# Pi1541_IEC.net
KiCad netlist of a schematic drawn in EAGLE
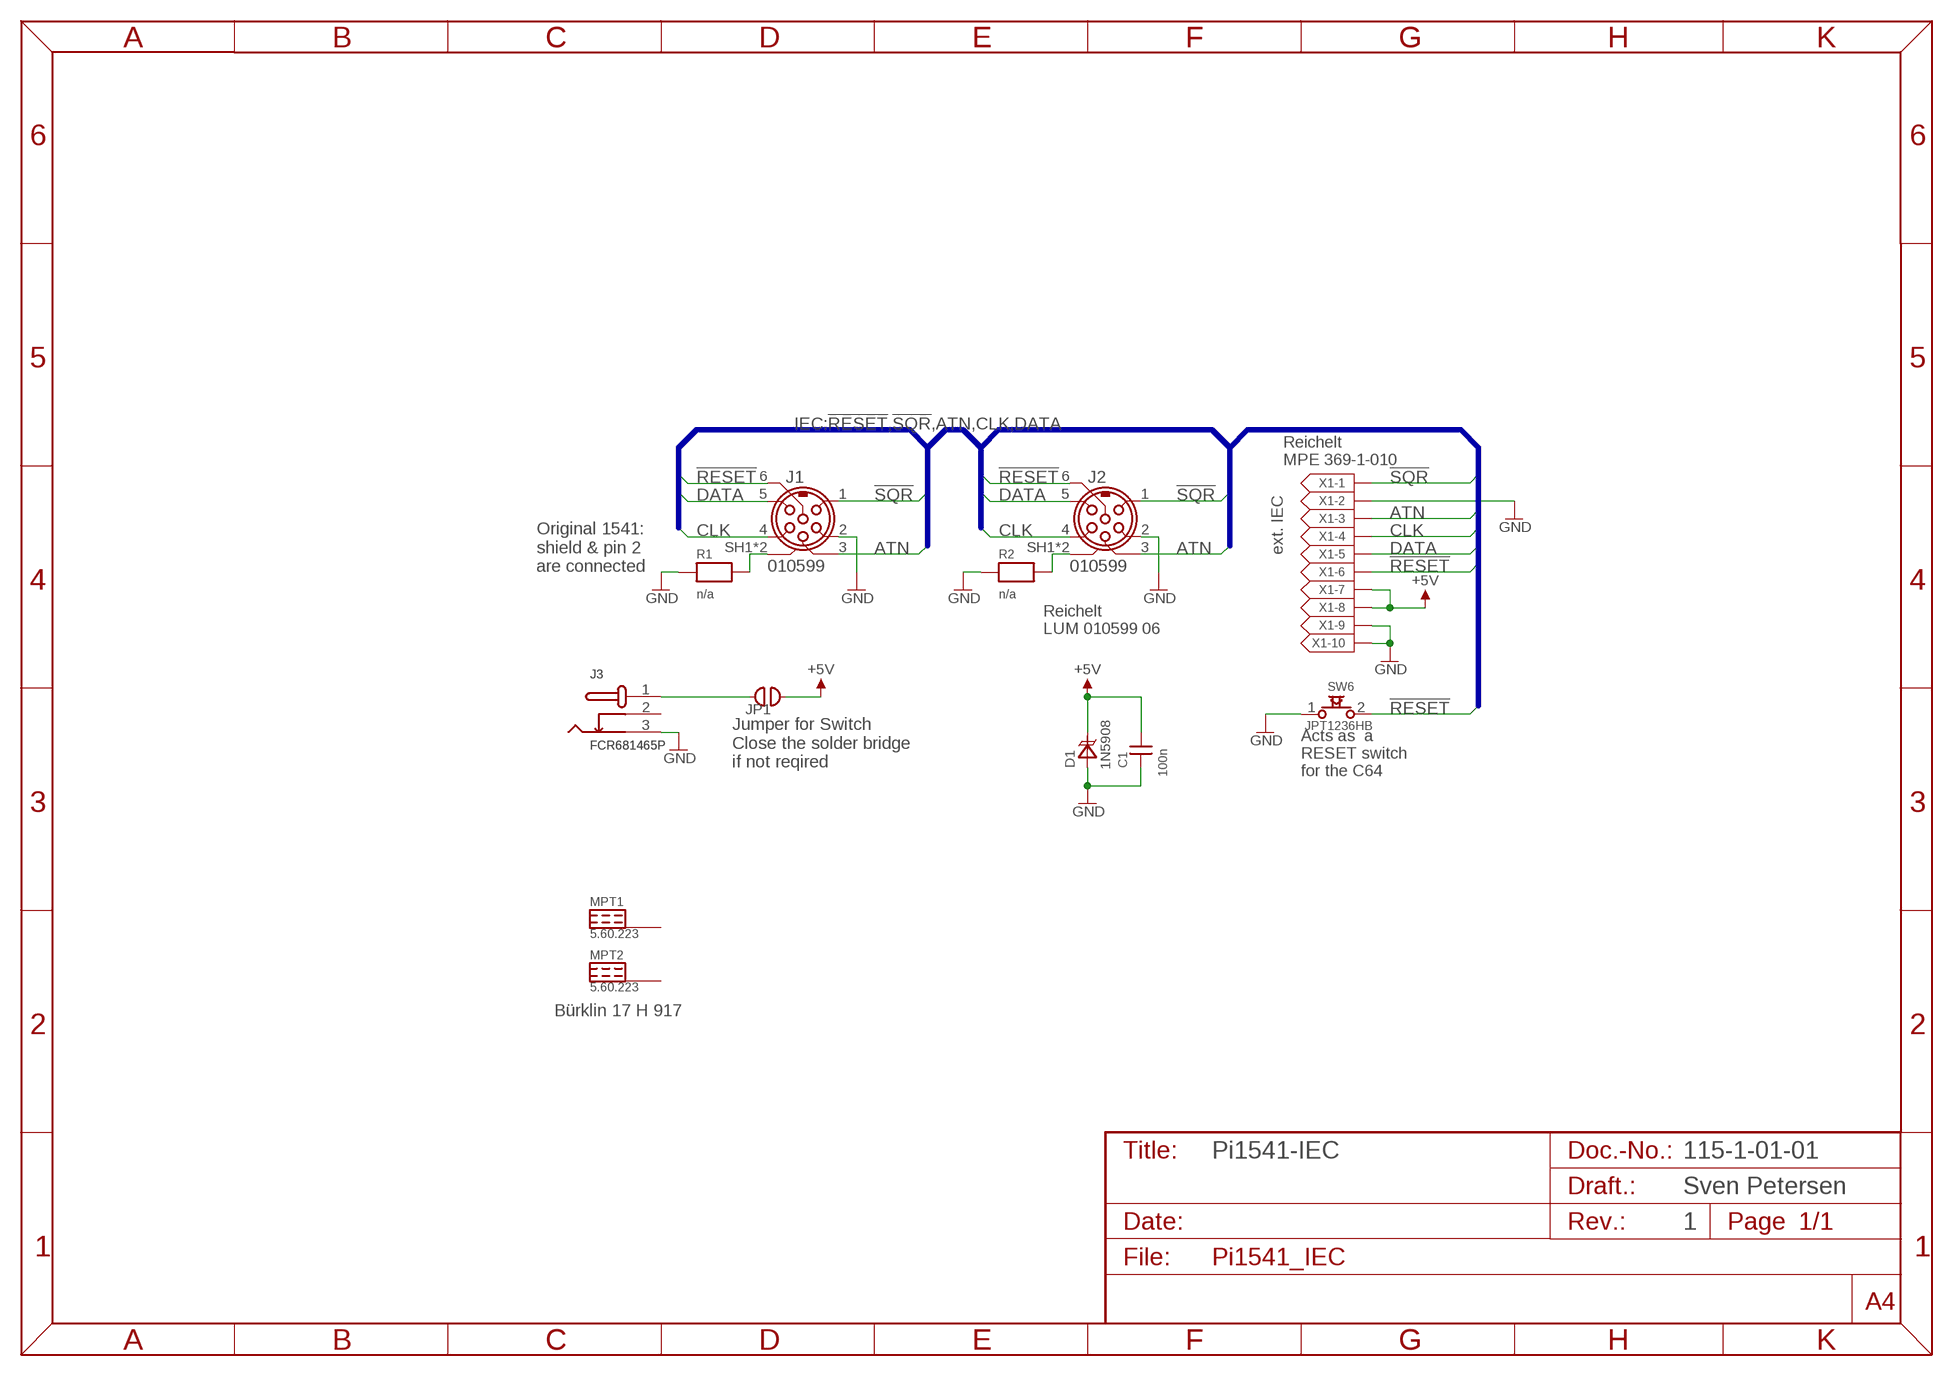
[diagram p0: schematic, sheet 1]

(export (version "E")
  (design (tool "Eeschema 10.0.6"))
  (components
    (comp (ref "C1")
      (value "100n")
      (footprint "eagle-import:C-2,5")
      (libsource (lib "eagle-import") (part "CAP01"))
    )
    (comp (ref "D1")
      (value "1N5908")
      (footprint "eagle-import:CB429")
      (libsource (lib "eagle-import") (part "1N5908"))
    )
    (comp (ref "J1")
      (value "010599")
      (footprint "eagle-import:010599")
      (libsource (lib "eagle-import") (part "010599"))
    )
    (comp (ref "J2")
      (value "010599")
      (footprint "eagle-import:010599")
      (libsource (lib "eagle-import") (part "010599"))
    )
    (comp (ref "J3")
      (value "FCR681465P")
      (footprint "eagle-import:FCR681465P")
      (libsource (lib "eagle-import") (part "FCR681465P"))
    )
    (comp (ref "JP1")
      (value "COMBI_2P")
      (footprint "eagle-import:COMBI-2P")
      (libsource (lib "eagle-import") (part "COMBI_2P"))
    )
    (comp (ref "MPT1")
      (value "5.60.223")
      (footprint "eagle-import:5.60.223")
      (libsource (lib "eagle-import") (part "5.60.223"))
    )
    (comp (ref "MPT2")
      (value "5.60.223")
      (footprint "eagle-import:5.60.223")
      (libsource (lib "eagle-import") (part "5.60.223"))
    )
    (comp (ref "R1")
      (value "n/a")
      (footprint "eagle-import:0805")
      (libsource (lib "eagle-import") (part "R-0805"))
    )
    (comp (ref "R2")
      (value "n/a")
      (footprint "eagle-import:0805")
      (libsource (lib "eagle-import") (part "R-0805"))
    )
    (comp (ref "SW6")
      (value "JPT1236HB")
      (footprint "eagle-import:JTP_1236HB")
      (libsource (lib "eagle-import") (part "JPT1236HB"))
    )
    (comp (ref "X1")
      (value "369-1-010")
      (footprint "eagle-import:MICMA10B")
      (libsource (lib "eagle-import") (part "MICMA10B-THT"))
    )
  )
  (nets
    (net (code "2") (name "+5V") (class "Default")
      (node (ref "C1") (pin "2") (pinfunction "2_2") (pintype "passive"))
      (node (ref "D1") (pin "K") (pinfunction "K_K") (pintype "passive"))
      (node (ref "JP1") (pin "2") (pinfunction "2_2") (pintype "passive"))
      (node (ref "X1") (pin "7") (pinfunction "1_7") (pintype "bidirectional"))
      (node (ref "X1") (pin "8") (pinfunction "1_8") (pintype "bidirectional"))
    )
    (net (code "3") (name "/ATN") (class "Default")
      (node (ref "J1") (pin "3") (pinfunction "3_3") (pintype "bidirectional"))
      (node (ref "J2") (pin "3") (pinfunction "3_3") (pintype "bidirectional"))
      (node (ref "X1") (pin "3") (pinfunction "1_3") (pintype "bidirectional"))
    )
    (net (code "4") (name "/CLK") (class "Default")
      (node (ref "J1") (pin "4") (pinfunction "4_4") (pintype "bidirectional"))
      (node (ref "J2") (pin "4") (pinfunction "4_4") (pintype "bidirectional"))
      (node (ref "X1") (pin "4") (pinfunction "1_4") (pintype "bidirectional"))
    )
    (net (code "5") (name "/DATA") (class "Default")
      (node (ref "J1") (pin "5") (pinfunction "5_5") (pintype "bidirectional"))
      (node (ref "J2") (pin "5") (pinfunction "5_5") (pintype "bidirectional"))
      (node (ref "X1") (pin "5") (pinfunction "1_5") (pintype "bidirectional"))
    )
    (net (code "7") (name "/~{RESET}") (class "Default")
      (node (ref "J1") (pin "6") (pinfunction "6_6") (pintype "bidirectional"))
      (node (ref "J2") (pin "6") (pinfunction "6_6") (pintype "bidirectional"))
      (node (ref "SW6") (pin "2") (pinfunction "2_2") (pintype "passive"))
      (node (ref "X1") (pin "6") (pinfunction "1_6") (pintype "bidirectional"))
    )
    (net (code "8") (name "/~{SQR}") (class "Default")
      (node (ref "J1") (pin "1") (pinfunction "1_1") (pintype "bidirectional"))
      (node (ref "J2") (pin "1") (pinfunction "1_1") (pintype "bidirectional"))
      (node (ref "X1") (pin "1") (pinfunction "1_1") (pintype "bidirectional"))
    )
    (net (code "9") (name "GND") (class "Default")
      (node (ref "C1") (pin "1") (pinfunction "1_1") (pintype "passive"))
      (node (ref "D1") (pin "A") (pinfunction "A_A") (pintype "passive"))
      (node (ref "J1") (pin "2") (pinfunction "2_2") (pintype "bidirectional"))
      (node (ref "J2") (pin "2") (pinfunction "2_2") (pintype "bidirectional"))
      (node (ref "J3") (pin "3") (pinfunction "3_3") (pintype "bidirectional"))
      (node (ref "R1") (pin "1") (pinfunction "1_1") (pintype "passive"))
      (node (ref "R2") (pin "1") (pinfunction "1_1") (pintype "passive"))
      (node (ref "SW6") (pin "1") (pinfunction "1_1") (pintype "passive"))
      (node (ref "X1") (pin "10") (pinfunction "1_10") (pintype "bidirectional"))
      (node (ref "X1") (pin "2") (pinfunction "1_2") (pintype "bidirectional"))
      (node (ref "X1") (pin "9") (pinfunction "1_9") (pintype "bidirectional"))
    )
    (net (code "10") (name "Net-(J1-SH-PadSH1)") (class "Default")
      (node (ref "J1") (pin "SH1") (pinfunction "SH_SH1") (pintype "bidirectional"))
      (node (ref "J1") (pin "SH2") (pinfunction "SH_SH2") (pintype "bidirectional"))
      (node (ref "R1") (pin "2") (pinfunction "2_2") (pintype "passive"))
    )
    (net (code "11") (name "Net-(J2-SH-PadSH1)") (class "Default")
      (node (ref "J2") (pin "SH1") (pinfunction "SH_SH1") (pintype "bidirectional"))
      (node (ref "J2") (pin "SH2") (pinfunction "SH_SH2") (pintype "bidirectional"))
      (node (ref "R2") (pin "2") (pinfunction "2_2") (pintype "passive"))
    )
    (net (code "12") (name "Net-(J3-Pad1)") (class "Default")
      (node (ref "J3") (pin "1") (pinfunction "1_1") (pintype "bidirectional"))
      (node (ref "JP1") (pin "1") (pinfunction "1_1") (pintype "passive"))
    )
    (net (code "13") (name "unconnected-(J3-Pad2)") (class "Default")
      (node (ref "J3") (pin "2") (pinfunction "2_2") (pintype "bidirectional"))
    )
    (net (code "14") (name "unconnected-(MPT1-P$1-Pad1)") (class "Default")
      (node (ref "MPT1") (pin "1") (pinfunction "P$1_1") (pintype "bidirectional"))
    )
    (net (code "15") (name "unconnected-(MPT2-P$1-Pad1)") (class "Default")
      (node (ref "MPT2") (pin "1") (pinfunction "P$1_1") (pintype "bidirectional"))
    )
  )
)
